# ESP32_with_USBC.net
KiCad netlist of a schematic drawn in Altium Designer
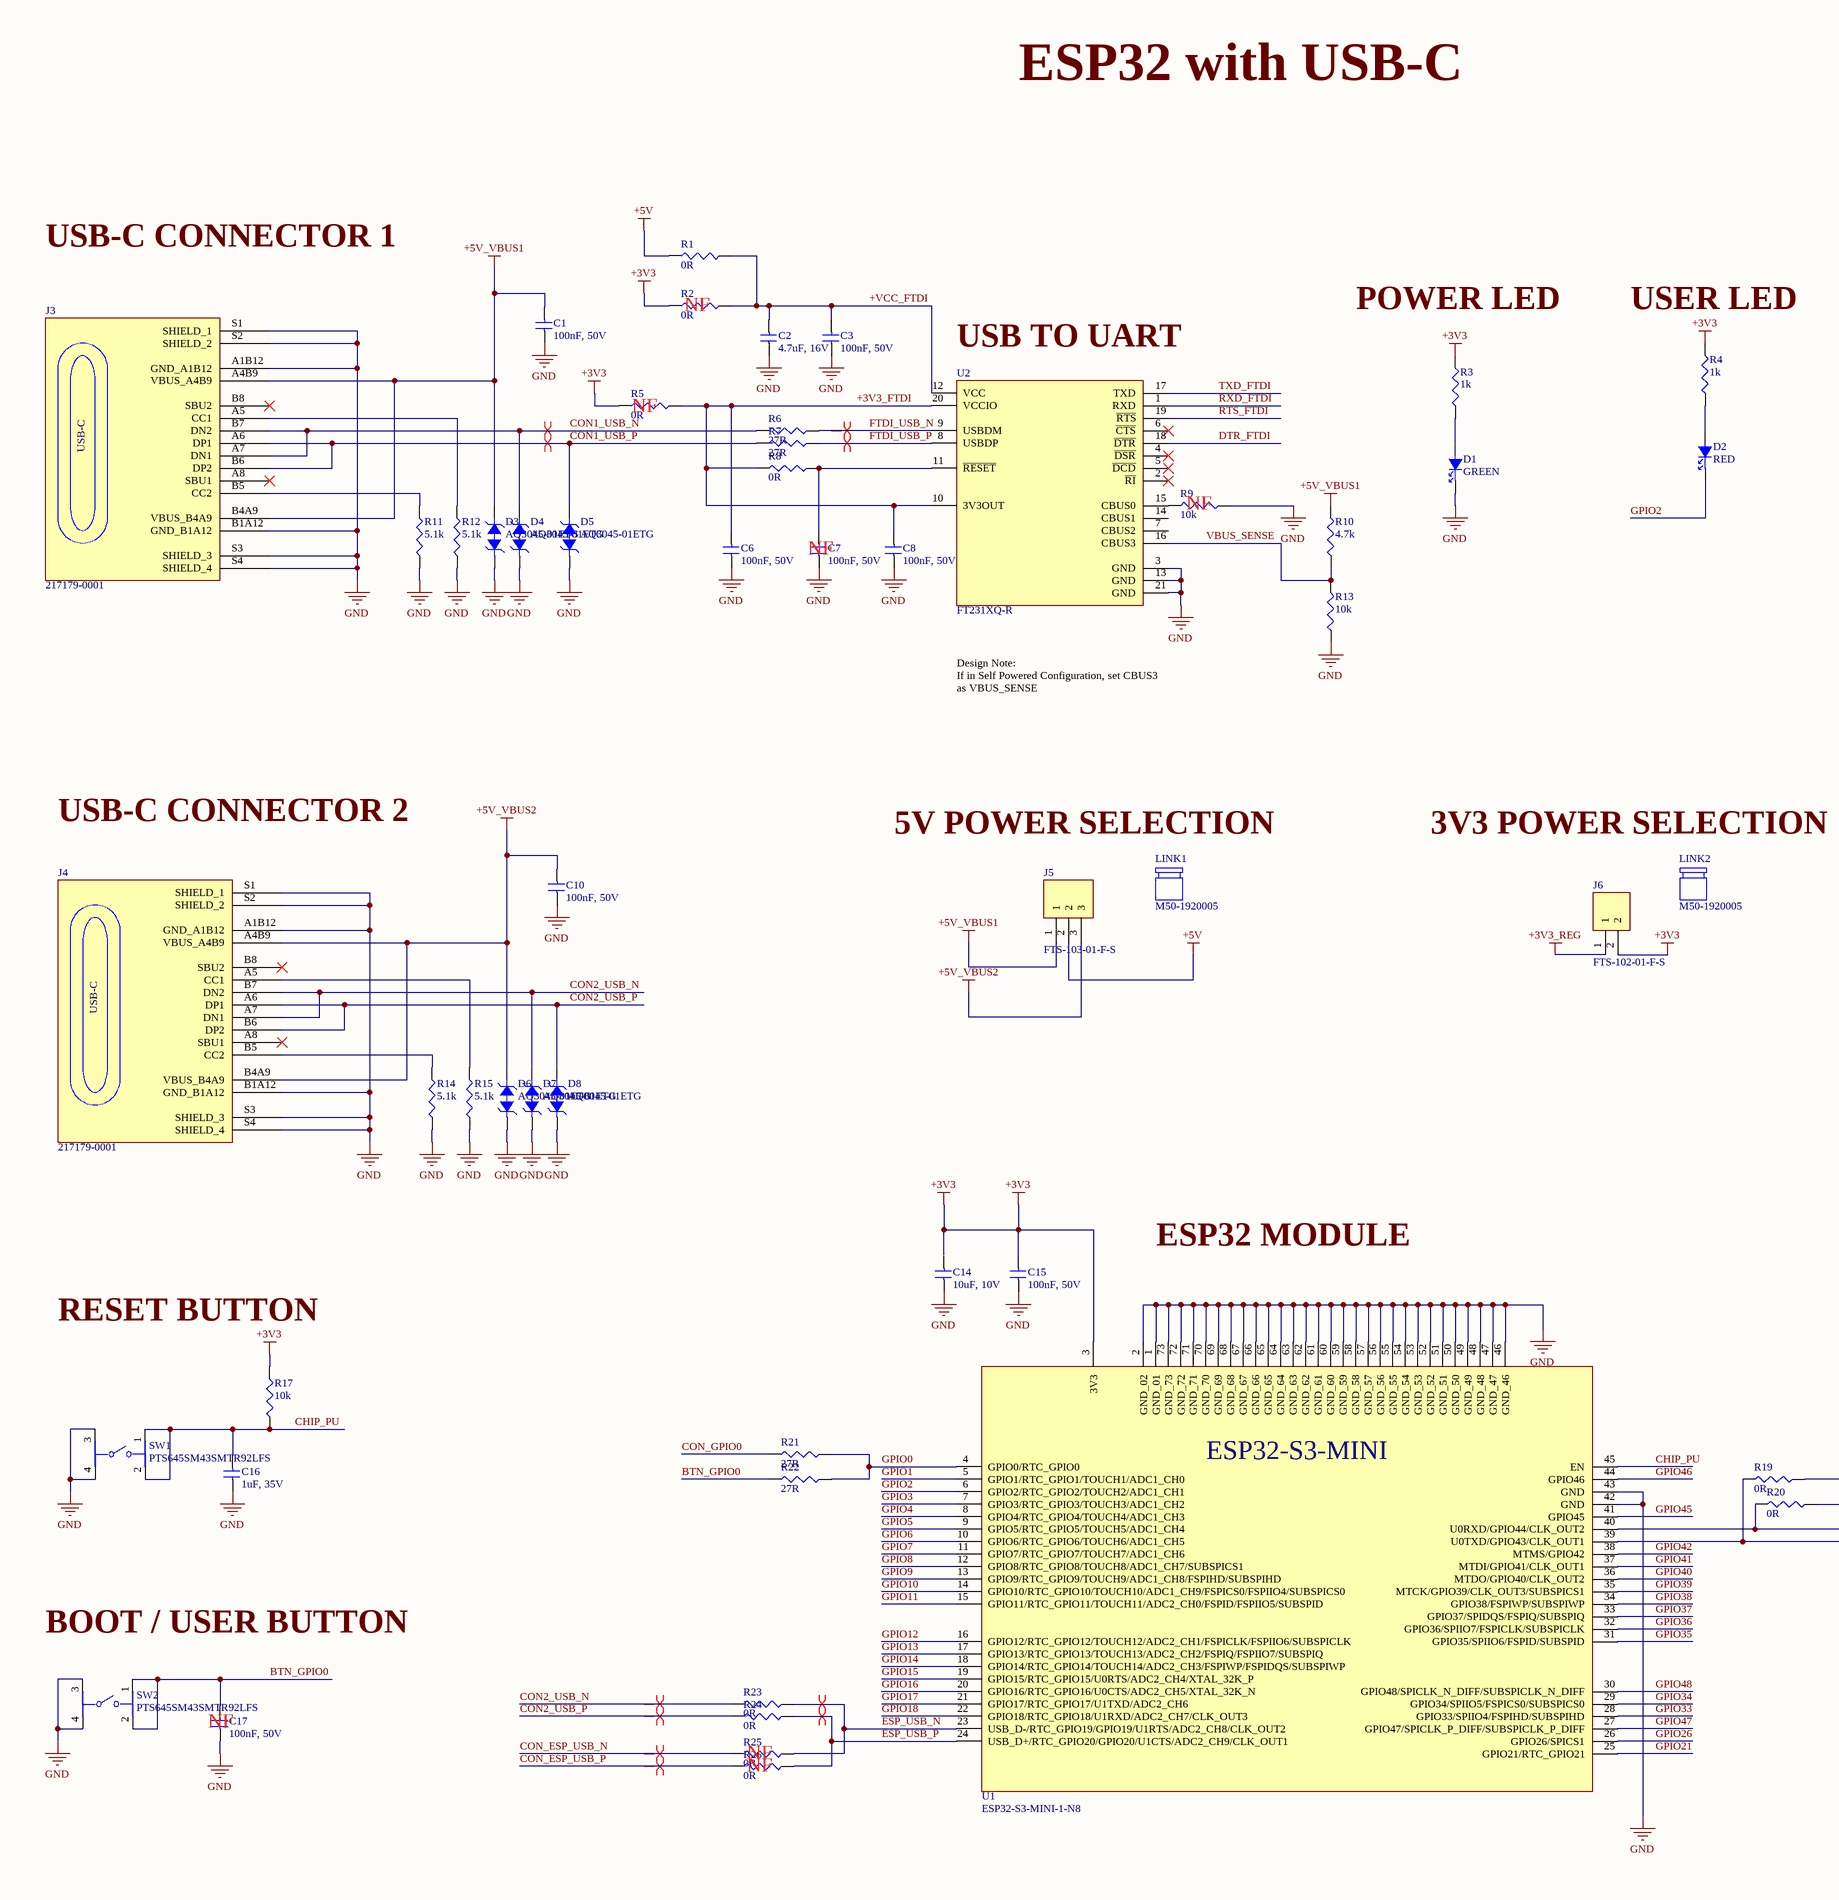
[diagram p0: ESP32 with USBC.SchDoc, left]
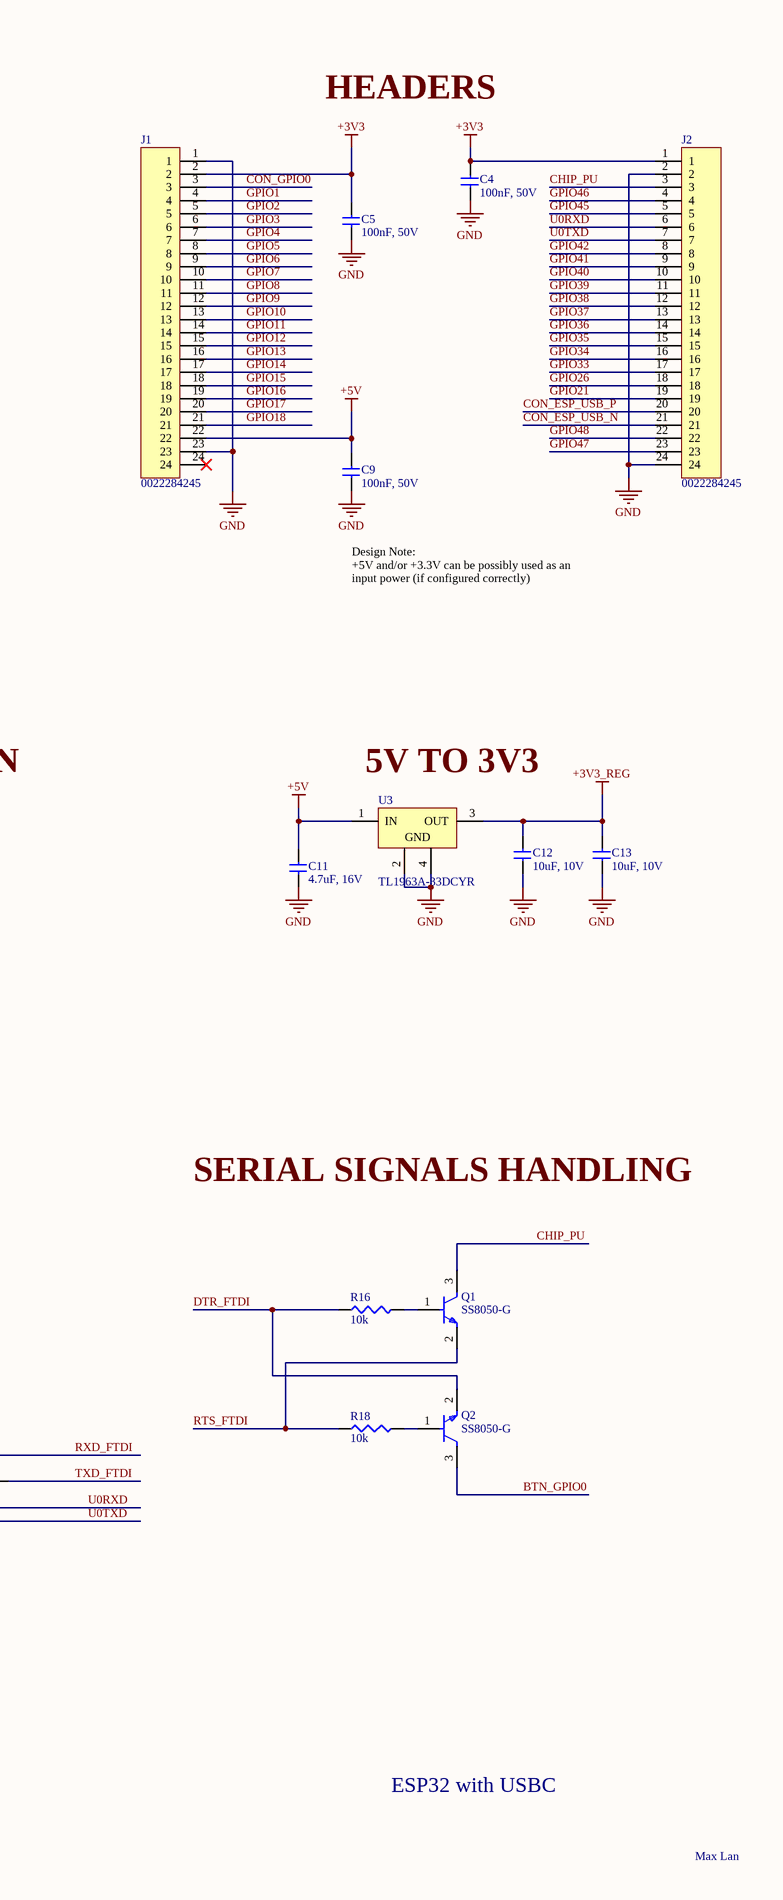
[diagram p1: ESP32 with USBC.SchDoc, right]

(export (version "E")
  (design (tool "Eeschema 10.0.6"))
  (components
    (comp (ref "C1")
      (value "100nF, 50V")
      (footprint "CAPC1005X55N")
      (description "CAP CER 0.1UF 50V X7R 0402")
      (fields
        (field (name "MANUFACTURER") "Samsung Electro-Mechanics")
        (field (name "MANUFACTURER PART NUMBER") "CL05B104KB5NNNC")
      )
      (libsource (lib "Schlib") (part "CL05B104KB5NNNC"))
    )
    (comp (ref "C2")
      (value "4.7uF, 16V")
      (footprint "CAPC1005X55N")
      (description "CAP CER 4.7UF 16V X5R 0402")
      (fields
        (field (name "MANUFACTURER") "Samsung Electro-Mechanics")
        (field (name "MANUFACTURER PART NUMBER") "CL05A475MO5NUNC")
      )
      (libsource (lib "Schlib") (part "CL05A475MO5NUNC"))
    )
    (comp (ref "C3")
      (value "100nF, 50V")
      (footprint "CAPC1005X55N")
      (description "CAP CER 0.1UF 50V X7R 0402")
      (fields
        (field (name "MANUFACTURER") "Samsung Electro-Mechanics")
        (field (name "MANUFACTURER PART NUMBER") "CL05B104KB5NNNC")
      )
      (libsource (lib "Schlib") (part "CL05B104KB5NNNC"))
    )
    (comp (ref "C4")
      (value "100nF, 50V")
      (footprint "CAPC1005X55N")
      (description "CAP CER 0.1UF 50V X7R 0402")
      (fields
        (field (name "MANUFACTURER") "Samsung Electro-Mechanics")
        (field (name "MANUFACTURER PART NUMBER") "CL05B104KB5NNNC")
      )
      (libsource (lib "Schlib") (part "CL05B104KB5NNNC"))
    )
    (comp (ref "C5")
      (value "100nF, 50V")
      (footprint "CAPC1005X55N")
      (description "CAP CER 0.1UF 50V X7R 0402")
      (fields
        (field (name "MANUFACTURER") "Samsung Electro-Mechanics")
        (field (name "MANUFACTURER PART NUMBER") "CL05B104KB5NNNC")
      )
      (libsource (lib "Schlib") (part "CL05B104KB5NNNC"))
    )
    (comp (ref "C6")
      (value "100nF, 50V")
      (footprint "CAPC1005X55N")
      (description "CAP CER 0.1UF 50V X7R 0402")
      (fields
        (field (name "MANUFACTURER") "Samsung Electro-Mechanics")
        (field (name "MANUFACTURER PART NUMBER") "CL05B104KB5NNNC")
      )
      (libsource (lib "Schlib") (part "CL05B104KB5NNNC"))
    )
    (comp (ref "C7")
      (value "100nF, 50V")
      (footprint "CAPC1005X55N")
      (description "CAP CER 0.1UF 50V X7R 0402")
      (fields
        (field (name "MANUFACTURER") "Samsung Electro-Mechanics")
        (field (name "MANUFACTURER PART NUMBER") "CL05B104KB5NNNC")
      )
      (libsource (lib "Schlib") (part "CL05B104KB5NNNC"))
    )
    (comp (ref "C8")
      (value "100nF, 50V")
      (footprint "CAPC1005X55N")
      (description "CAP CER 0.1UF 50V X7R 0402")
      (fields
        (field (name "MANUFACTURER") "Samsung Electro-Mechanics")
        (field (name "MANUFACTURER PART NUMBER") "CL05B104KB5NNNC")
      )
      (libsource (lib "Schlib") (part "CL05B104KB5NNNC"))
    )
    (comp (ref "C9")
      (value "100nF, 50V")
      (footprint "CAPC1005X55N")
      (description "CAP CER 0.1UF 50V X7R 0402")
      (fields
        (field (name "MANUFACTURER") "Samsung Electro-Mechanics")
        (field (name "MANUFACTURER PART NUMBER") "CL05B104KB5NNNC")
      )
      (libsource (lib "Schlib") (part "CL05B104KB5NNNC"))
    )
    (comp (ref "C10")
      (value "100nF, 50V")
      (footprint "CAPC1005X55N")
      (description "CAP CER 0.1UF 50V X7R 0402")
      (fields
        (field (name "MANUFACTURER") "Samsung Electro-Mechanics")
        (field (name "MANUFACTURER PART NUMBER") "CL05B104KB5NNNC")
      )
      (libsource (lib "Schlib") (part "CL05B104KB5NNNC"))
    )
    (comp (ref "C11")
      (value "4.7uF, 16V")
      (footprint "CAPC1005X55N")
      (description "CAP CER 4.7UF 16V X5R 0402")
      (fields
        (field (name "MANUFACTURER") "Samsung Electro-Mechanics")
        (field (name "MANUFACTURER PART NUMBER") "CL05A475MO5NUNC")
      )
      (libsource (lib "Schlib") (part "CL05A475MO5NUNC"))
    )
    (comp (ref "C12")
      (value "10uF, 10V")
      (footprint "CAPC1005X55N")
      (description "10 µF ±20% 10V Ceramic Capacitor X5R 0402 (1005 Metric)")
      (fields
        (field (name "MANUFACTURER") "Samsung Electro-Mechanics")
        (field (name "MANUFACTURER PART NUMBER") "CL05A106MP5NRNC")
      )
      (libsource (lib "Schlib") (part "CL05A106MP5NRNC"))
    )
    (comp (ref "C13")
      (value "10uF, 10V")
      (footprint "CAPC1005X55N")
      (description "10 µF ±20% 10V Ceramic Capacitor X5R 0402 (1005 Metric)")
      (fields
        (field (name "MANUFACTURER") "Samsung Electro-Mechanics")
        (field (name "MANUFACTURER PART NUMBER") "CL05A106MP5NRNC")
      )
      (libsource (lib "Schlib") (part "CL05A106MP5NRNC"))
    )
    (comp (ref "C14")
      (value "10uF, 10V")
      (footprint "CAPC1005X55N")
      (description "10 µF ±20% 10V Ceramic Capacitor X5R 0402 (1005 Metric)")
      (fields
        (field (name "MANUFACTURER") "Samsung Electro-Mechanics")
        (field (name "MANUFACTURER PART NUMBER") "CL05A106MP5NRNC")
      )
      (libsource (lib "Schlib") (part "CL05A106MP5NRNC"))
    )
    (comp (ref "C15")
      (value "100nF, 50V")
      (footprint "CAPC1005X55N")
      (description "CAP CER 0.1UF 50V X7R 0402")
      (fields
        (field (name "MANUFACTURER") "Samsung Electro-Mechanics")
        (field (name "MANUFACTURER PART NUMBER") "CL05B104KB5NNNC")
      )
      (libsource (lib "Schlib") (part "CL05B104KB5NNNC"))
    )
    (comp (ref "C16")
      (value "1uF, 35V")
      (footprint "CAPC1005X55N")
      (description "CAP CER 1UF 35V X5R 0402")
      (fields
        (field (name "MANUFACTURER") "Samsung Electro-Mechanics")
        (field (name "MANUFACTURER PART NUMBER") "CL05A105KL5NRNC")
      )
      (libsource (lib "Schlib") (part "CL05A105KL5NRNC"))
    )
    (comp (ref "C17")
      (value "100nF, 50V")
      (footprint "CAPC1005X55N")
      (description "CAP CER 0.1UF 50V X7R 0402")
      (fields
        (field (name "MANUFACTURER") "Samsung Electro-Mechanics")
        (field (name "MANUFACTURER PART NUMBER") "CL05B104KB5NNNC")
      )
      (libsource (lib "Schlib") (part "CL05B104KB5NNNC"))
    )
    (comp (ref "D1")
      (value "GREEN")
      (footprint "LED0402G")
      (description "LED YLW-GRN 0402 SMD")
      (fields
        (field (name "MANUFACTURER") "Vishay")
        (field (name "MANUFACTURER PART NUMBER") "VLMG1500-GS08")
      )
      (libsource (lib "Schlib") (part "VLMG1500-GS08"))
    )
    (comp (ref "D2")
      (value "RED")
      (footprint "LED0402R")
      (description "LED RED 0402 SMD")
      (fields
        (field (name "MANUFACTURER") "Vishay")
        (field (name "MANUFACTURER PART NUMBER") "VLMS1500-GS08")
      )
      (libsource (lib "Schlib") (part "VLMS1500-GS08"))
    )
    (comp (ref "D3")
      (value "AQ3045-01ETG")
      (footprint "SOD882")
      (description "TVS DIODE 5.3VWM 12VC SOD882")
      (fields (field (name "MANUFACTURER") "Littelfuse") (field (name "LCSC PART NUMBER") "C3710326"))
      (libsource (lib "Schlib") (part "AQ3045-01ETG"))
    )
    (comp (ref "D4")
      (value "AQ3045-01ETG")
      (footprint "SOD882")
      (description "TVS DIODE 5.3VWM 12VC SOD882")
      (fields (field (name "MANUFACTURER") "Littelfuse") (field (name "LCSC PART NUMBER") "C3710326"))
      (libsource (lib "Schlib") (part "AQ3045-01ETG"))
    )
    (comp (ref "D5")
      (value "AQ3045-01ETG")
      (footprint "SOD882")
      (description "TVS DIODE 5.3VWM 12VC SOD882")
      (fields (field (name "MANUFACTURER") "Littelfuse") (field (name "LCSC PART NUMBER") "C3710326"))
      (libsource (lib "Schlib") (part "AQ3045-01ETG"))
    )
    (comp (ref "D6")
      (value "AQ3045-01ETG")
      (footprint "SOD882")
      (description "TVS DIODE 5.3VWM 12VC SOD882")
      (fields (field (name "MANUFACTURER") "Littelfuse") (field (name "LCSC PART NUMBER") "C3710326"))
      (libsource (lib "Schlib") (part "AQ3045-01ETG"))
    )
    (comp (ref "D7")
      (value "AQ3045-01ETG")
      (footprint "SOD882")
      (description "TVS DIODE 5.3VWM 12VC SOD882")
      (fields (field (name "MANUFACTURER") "Littelfuse") (field (name "LCSC PART NUMBER") "C3710326"))
      (libsource (lib "Schlib") (part "AQ3045-01ETG"))
    )
    (comp (ref "D8")
      (value "AQ3045-01ETG")
      (footprint "SOD882")
      (description "TVS DIODE 5.3VWM 12VC SOD882")
      (fields (field (name "MANUFACTURER") "Littelfuse") (field (name "LCSC PART NUMBER") "C3710326"))
      (libsource (lib "Schlib") (part "AQ3045-01ETG"))
    )
    (comp (ref "J1")
      (value "0022284245")
      (footprint "HDR_1X24_2.54MM")
      (description "CONN HEADER VERT 24POS 2.54MM")
      (fields (field (name "MANUFACTURER") "Molex") (field (name "MANUFACTURER PART NUMBER") "22-28-4245"))
      (libsource (lib "Schlib") (part "0022284245"))
    )
    (comp (ref "J2")
      (value "0022284245")
      (footprint "HDR_1X24_2.54MM")
      (description "CONN HEADER VERT 24POS 2.54MM")
      (fields (field (name "MANUFACTURER") "Molex") (field (name "MANUFACTURER PART NUMBER") "22-28-4245"))
      (libsource (lib "") (part "0022284245_1"))
    )
    (comp (ref "J3")
      (value "217179-0001")
      (footprint "FP-2171790001-MFG")
      (description "CONN RCP USB2.0 TYP C 24P SMD RA")
      (fields (field (name "MANUFACTURER") "Molex") (field (name "LCSC PART NUMBER") "C3197684"))
      (libsource (lib "Schlib") (part "217179-0001"))
    )
    (comp (ref "J4")
      (value "217179-0001")
      (footprint "FP-2171790001-MFG")
      (description "CONN RCP USB2.0 TYP C 24P SMD RA")
      (fields (field (name "MANUFACTURER") "Molex") (field (name "LCSC PART NUMBER") "C3197684"))
      (libsource (lib "Schlib") (part "217179-0001"))
    )
    (comp (ref "J5")
      (value "FTS-103-01-F-S")
      (footprint "HDR_1X3_1.27MM")
      (description "CONN HEADER VERT 3POS 1.27MM")
      (fields (field (name "MANUFACTURER") "Samtec") (field (name "LCSC PART NUMBER") "C3333578"))
      (libsource (lib "Schlib") (part "FTS-103-01-F-S"))
    )
    (comp (ref "J6")
      (value "FTS-102-01-F-S")
      (footprint "HDR_1X2_1.27MM")
      (description "CONN HEADER VERT 2POS 1.27MM")
      (fields (field (name "MANUFACTURER") "Samtec") (field (name "LCSC PART NUMBER") "C6045317"))
      (libsource (lib "Schlib") (part "FTS-102-01-F-S"))
    )
    (comp (ref "LINK1")
      (value "M50-1920005")
      (description "CONN SHUNT 1.27MM RED")
      (fields (field (name "MANUFACTURER") "Harwin") (field (name "LCSC PART NUMBER") "C6985646"))
      (libsource (lib "Schlib") (part "M50-1920005"))
    )
    (comp (ref "LINK2")
      (value "M50-1920005")
      (description "CONN SHUNT 1.27MM RED")
      (fields (field (name "MANUFACTURER") "Harwin") (field (name "LCSC PART NUMBER") "C6985646"))
      (libsource (lib "Schlib") (part "M50-1920005"))
    )
    (comp (ref "Q1")
      (value "SS8050-G")
      (footprint "FP-SS8050-G-IPC_B")
      (description "TRANS NPN 25V 1.5A SOT-23-3")
      (fields (field (name "MANUFACTURER") "Comchip") (field (name "LCSC PART NUMBER") "C164886"))
      (libsource (lib "Schlib") (part "SS8050-G"))
    )
    (comp (ref "Q2")
      (value "SS8050-G")
      (footprint "FP-SS8050-G-IPC_B")
      (description "TRANS NPN 25V 1.5A SOT-23-3")
      (fields (field (name "MANUFACTURER") "Comchip") (field (name "LCSC PART NUMBER") "C164886"))
      (libsource (lib "Schlib") (part "SS8050-G"))
    )
    (comp (ref "R1")
      (value "0R")
      (footprint "RESC1005X37N")
      (description "RES 0 OHM JUMPER 1/16W 0402")
      (fields
        (field (name "MANUFACTURER") "Yageo Group")
        (field (name "MANUFACTURER PART NUMBER") "RC0402JR-070RL")
      )
      (libsource (lib "Schlib") (part "RC0402JR-070RL"))
    )
    (comp (ref "R2")
      (value "0R")
      (footprint "RESC1005X37N")
      (description "RES 0 OHM JUMPER 1/16W 0402")
      (fields
        (field (name "MANUFACTURER") "Yageo Group")
        (field (name "MANUFACTURER PART NUMBER") "RC0402JR-070RL")
      )
      (libsource (lib "Schlib") (part "RC0402JR-070RL"))
    )
    (comp (ref "R3")
      (value "1k")
      (footprint "RESC1005X37N")
      (description "RES 1K OHM 1% 1/16W 0402")
      (fields
        (field (name "MANUFACTURER") "Yageo Group")
        (field (name "MANUFACTURER PART NUMBER") "RC0402FR-071KL")
      )
      (libsource (lib "Schlib") (part "RC0402FR-071KL"))
    )
    (comp (ref "R4")
      (value "1k")
      (footprint "RESC1005X37N")
      (description "RES 1K OHM 1% 1/16W 0402")
      (fields
        (field (name "MANUFACTURER") "Yageo Group")
        (field (name "MANUFACTURER PART NUMBER") "RC0402FR-071KL")
      )
      (libsource (lib "Schlib") (part "RC0402FR-071KL"))
    )
    (comp (ref "R5")
      (value "0R")
      (footprint "RESC1005X37N")
      (description "RES 0 OHM JUMPER 1/16W 0402")
      (fields
        (field (name "MANUFACTURER") "Yageo Group")
        (field (name "MANUFACTURER PART NUMBER") "RC0402JR-070RL")
      )
      (libsource (lib "Schlib") (part "RC0402JR-070RL"))
    )
    (comp (ref "R6")
      (value "27R")
      (footprint "RESC1005X37N")
      (description "RES 27 OHM 1% 1/16W 0402")
      (fields
        (field (name "MANUFACTURER") "Yageo Group")
        (field (name "MANUFACTURER PART NUMBER") "RC0402FR-0727RL")
      )
      (libsource (lib "Schlib") (part "RC0402FR-0727RL"))
    )
    (comp (ref "R7")
      (value "27R")
      (footprint "RESC1005X37N")
      (description "RES 27 OHM 1% 1/16W 0402")
      (fields
        (field (name "MANUFACTURER") "Yageo Group")
        (field (name "MANUFACTURER PART NUMBER") "RC0402FR-0727RL")
      )
      (libsource (lib "Schlib") (part "RC0402FR-0727RL"))
    )
    (comp (ref "R8")
      (value "0R")
      (footprint "RESC1005X37N")
      (description "RES 0 OHM JUMPER 1/16W 0402")
      (fields
        (field (name "MANUFACTURER") "Yageo Group")
        (field (name "MANUFACTURER PART NUMBER") "RC0402JR-070RL")
      )
      (libsource (lib "Schlib") (part "RC0402JR-070RL"))
    )
    (comp (ref "R9")
      (value "10k")
      (footprint "RESC1005X37N")
      (description "RES SMD 10K OHM 1% 1/16W 0402")
      (fields
        (field (name "MANUFACTURER") "Yageo Group")
        (field (name "MANUFACTURER PART NUMBER") "AF0402FR-0710KL")
      )
      (libsource (lib "Schlib") (part "AF0402FR-0710KL"))
    )
    (comp (ref "R10")
      (value "4.7k")
      (footprint "RESC1005X37N")
      (description "RES SMD 4.7K OHM 1% 1/16W 0402")
      (fields
        (field (name "MANUFACTURER") "Yageo Group")
        (field (name "MANUFACTURER PART NUMBER") "RT0402FRE074K7L")
      )
      (libsource (lib "Schlib") (part "RT0402FRE074K7L"))
    )
    (comp (ref "R11")
      (value "5.1k")
      (footprint "RESC1005X37N")
      (description "RES SMD 5.1K OHM 1% 1/16W 0402")
      (fields
        (field (name "MANUFACTURER") "Yageo Group")
        (field (name "MANUFACTURER PART NUMBER") "AC0402FR-075K1L")
      )
      (libsource (lib "Schlib") (part "AC0402FR-075K1L"))
    )
    (comp (ref "R12")
      (value "5.1k")
      (footprint "RESC1005X37N")
      (description "RES SMD 5.1K OHM 1% 1/16W 0402")
      (fields
        (field (name "MANUFACTURER") "Yageo Group")
        (field (name "MANUFACTURER PART NUMBER") "AC0402FR-075K1L")
      )
      (libsource (lib "Schlib") (part "AC0402FR-075K1L"))
    )
    (comp (ref "R13")
      (value "10k")
      (footprint "RESC1005X37N")
      (description "RES SMD 10K OHM 1% 1/16W 0402")
      (fields
        (field (name "MANUFACTURER") "Yageo Group")
        (field (name "MANUFACTURER PART NUMBER") "AF0402FR-0710KL")
      )
      (libsource (lib "Schlib") (part "AF0402FR-0710KL"))
    )
    (comp (ref "R14")
      (value "5.1k")
      (footprint "RESC1005X37N")
      (description "RES SMD 5.1K OHM 1% 1/16W 0402")
      (fields
        (field (name "MANUFACTURER") "Yageo Group")
        (field (name "MANUFACTURER PART NUMBER") "AC0402FR-075K1L")
      )
      (libsource (lib "Schlib") (part "AC0402FR-075K1L"))
    )
    (comp (ref "R15")
      (value "5.1k")
      (footprint "RESC1005X37N")
      (description "RES SMD 5.1K OHM 1% 1/16W 0402")
      (fields
        (field (name "MANUFACTURER") "Yageo Group")
        (field (name "MANUFACTURER PART NUMBER") "AC0402FR-075K1L")
      )
      (libsource (lib "Schlib") (part "AC0402FR-075K1L"))
    )
    (comp (ref "R16")
      (value "10k")
      (footprint "RESC1005X37N")
      (description "RES SMD 10K OHM 1% 1/16W 0402")
      (fields
        (field (name "MANUFACTURER") "Yageo Group")
        (field (name "MANUFACTURER PART NUMBER") "AF0402FR-0710KL")
      )
      (libsource (lib "Schlib") (part "AF0402FR-0710KL"))
    )
    (comp (ref "R17")
      (value "10k")
      (footprint "RESC1005X37N")
      (description "RES SMD 10K OHM 1% 1/16W 0402")
      (fields
        (field (name "MANUFACTURER") "Yageo Group")
        (field (name "MANUFACTURER PART NUMBER") "AF0402FR-0710KL")
      )
      (libsource (lib "Schlib") (part "AF0402FR-0710KL"))
    )
    (comp (ref "R18")
      (value "10k")
      (footprint "RESC1005X37N")
      (description "RES SMD 10K OHM 1% 1/16W 0402")
      (fields
        (field (name "MANUFACTURER") "Yageo Group")
        (field (name "MANUFACTURER PART NUMBER") "AF0402FR-0710KL")
      )
      (libsource (lib "Schlib") (part "AF0402FR-0710KL"))
    )
    (comp (ref "R19")
      (value "0R")
      (footprint "RESC1005X37N")
      (description "RES 0 OHM JUMPER 1/16W 0402")
      (fields
        (field (name "MANUFACTURER") "Yageo Group")
        (field (name "MANUFACTURER PART NUMBER") "RC0402JR-070RL")
      )
      (libsource (lib "Schlib") (part "RC0402JR-070RL"))
    )
    (comp (ref "R20")
      (value "0R")
      (footprint "RESC1005X37N")
      (description "RES 0 OHM JUMPER 1/16W 0402")
      (fields
        (field (name "MANUFACTURER") "Yageo Group")
        (field (name "MANUFACTURER PART NUMBER") "RC0402JR-070RL")
      )
      (libsource (lib "Schlib") (part "RC0402JR-070RL"))
    )
    (comp (ref "R21")
      (value "27R")
      (footprint "RESC1005X37N")
      (description "RES 27 OHM 1% 1/16W 0402")
      (fields
        (field (name "MANUFACTURER") "Yageo Group")
        (field (name "MANUFACTURER PART NUMBER") "RC0402FR-0727RL")
      )
      (libsource (lib "Schlib") (part "RC0402FR-0727RL"))
    )
    (comp (ref "R22")
      (value "27R")
      (footprint "RESC1005X37N")
      (description "RES 27 OHM 1% 1/16W 0402")
      (fields
        (field (name "MANUFACTURER") "Yageo Group")
        (field (name "MANUFACTURER PART NUMBER") "RC0402FR-0727RL")
      )
      (libsource (lib "Schlib") (part "RC0402FR-0727RL"))
    )
    (comp (ref "R23")
      (value "0R")
      (footprint "RESC1005X37N")
      (description "RES 0 OHM JUMPER 1/16W 0402")
      (fields
        (field (name "MANUFACTURER") "Yageo Group")
        (field (name "MANUFACTURER PART NUMBER") "RC0402JR-070RL")
      )
      (libsource (lib "Schlib") (part "RC0402JR-070RL"))
    )
    (comp (ref "R24")
      (value "0R")
      (footprint "RESC1005X37N")
      (description "RES 0 OHM JUMPER 1/16W 0402")
      (fields
        (field (name "MANUFACTURER") "Yageo Group")
        (field (name "MANUFACTURER PART NUMBER") "RC0402JR-070RL")
      )
      (libsource (lib "Schlib") (part "RC0402JR-070RL"))
    )
    (comp (ref "R25")
      (value "0R")
      (footprint "RESC1005X37N")
      (description "RES 0 OHM JUMPER 1/16W 0402")
      (fields
        (field (name "MANUFACTURER") "Yageo Group")
        (field (name "MANUFACTURER PART NUMBER") "RC0402JR-070RL")
      )
      (libsource (lib "Schlib") (part "RC0402JR-070RL"))
    )
    (comp (ref "R26")
      (value "0R")
      (footprint "RESC1005X37N")
      (description "RES 0 OHM JUMPER 1/16W 0402")
      (fields
        (field (name "MANUFACTURER") "Yageo Group")
        (field (name "MANUFACTURER PART NUMBER") "RC0402JR-070RL")
      )
      (libsource (lib "Schlib") (part "RC0402JR-070RL"))
    )
    (comp (ref "SW1")
      (value "PTS645SM43SMTR92LFS")
      (footprint "FP-PTS645SM43SMTR92LFS-MFG")
      (description "SWITCH TACTILE SPST-NO 0.05A 12V")
      (fields (field (name "MANUFACTURER") "C&K Components") (field (name "LCSC PART NUMBER") "C221880"))
      (libsource (lib "Schlib") (part "PTS645SM43SMTR92LFS"))
    )
    (comp (ref "SW2")
      (value "PTS645SM43SMTR92LFS")
      (footprint "FP-PTS645SM43SMTR92LFS-MFG")
      (description "SWITCH TACTILE SPST-NO 0.05A 12V")
      (fields (field (name "MANUFACTURER") "C&K Components") (field (name "LCSC PART NUMBER") "C221880"))
      (libsource (lib "Schlib") (part "PTS645SM43SMTR92LFS"))
    )
    (comp (ref "U1")
      (value "ESP32-S3-MINI-1-N8")
      (footprint "XCVR_ESP32-S3-MINI-1-N8")
      (description "SMD module, ESP32-S3FN8, 8 MB SPI flash, PCB antenna")
      (fields (field (name "MANUFACTURER") "Espressif Systems") (field (name "LCSC PART NUMBER") "C2913206"))
      (libsource (lib "Schlib") (part "ESP32-S3-MINI-1-N8"))
    )
    (comp (ref "U2")
      (value "FT231XQ-R")
      (footprint "FP-QFN-20-IPC_B")
      (description "IC USB SERIAL FULL UART 20QFN")
      (fields (field (name "MANUFACTURER") "FTDI") (field (name "LCSC PART NUMBER") "C132159"))
      (libsource (lib "Schlib") (part "FT231XQ-R"))
    )
    (comp (ref "U3")
      (value "TL1963A-33DCYR")
      (footprint "DCY0004A_N")
      (description "IC REG LIN 3.3V 1.5A SOT-223-4")
      (fields (field (name "MANUFACTURER") "Texas Instruments") (field (name "LCSC PART NUMBER") "C181262"))
      (libsource (lib "Schlib") (part "TL1963A-33DCYR"))
    )
  )
  (nets
    (net (code "1") (name "+3V3") (class "Default")
      (node (ref "C15") (pin "2") (pinfunction "2_2") (pintype "passive"))
      (node (ref "C4") (pin "2") (pinfunction "2_2") (pintype "passive"))
      (node (ref "C5") (pin "2") (pinfunction "2_2") (pintype "passive"))
      (node (ref "J1") (pin "2") (pinfunction "2_2") (pintype "passive"))
      (node (ref "J2") (pin "1") (pinfunction "1_1") (pintype "passive"))
      (node (ref "J6") (pin "2") (pinfunction "2_2") (pintype "passive"))
      (node (ref "R17") (pin "2") (pinfunction "2_2") (pintype "passive"))
      (node (ref "R2") (pin "1") (pinfunction "1_1") (pintype "passive"))
      (node (ref "R3") (pin "2") (pinfunction "2_2") (pintype "passive"))
      (node (ref "R4") (pin "2") (pinfunction "2_2") (pintype "passive"))
      (node (ref "R5") (pin "1") (pinfunction "1_1") (pintype "passive"))
      (node (ref "U1") (pin "3") (pinfunction "3V3_3") (pintype "passive"))
    )
    (net (code "2") (name "+3V3_REG") (class "Default")
      (node (ref "C12") (pin "2") (pinfunction "2_2") (pintype "passive"))
      (node (ref "C13") (pin "2") (pinfunction "2_2") (pintype "passive"))
      (node (ref "J6") (pin "1") (pinfunction "1_1") (pintype "passive"))
      (node (ref "U3") (pin "3") (pinfunction "OUT_3") (pintype "power_in"))
    )
    (net (code "3") (name "+5V") (class "Default")
      (node (ref "C11") (pin "2") (pinfunction "2_2") (pintype "passive"))
      (node (ref "C9") (pin "2") (pinfunction "2_2") (pintype "passive"))
      (node (ref "J1") (pin "22") (pinfunction "22_22") (pintype "passive"))
      (node (ref "J5") (pin "2") (pinfunction "2_2") (pintype "passive"))
      (node (ref "R1") (pin "1") (pinfunction "1_1") (pintype "passive"))
      (node (ref "U3") (pin "1") (pinfunction "IN_1") (pintype "power_in"))
    )
    (net (code "4") (name "+5V_VBUS1") (class "Default")
      (node (ref "C1") (pin "2") (pinfunction "2_2") (pintype "passive"))
      (node (ref "D3") (pin "2") (pinfunction "2_2") (pintype "passive"))
      (node (ref "J3") (pin "A4B9") (pinfunction "VBUS_A4B9_A4B9") (pintype "passive"))
      (node (ref "J3") (pin "B4A9") (pinfunction "VBUS_B4A9_B4A9") (pintype "passive"))
      (node (ref "J5") (pin "1") (pinfunction "1_1") (pintype "passive"))
      (node (ref "R10") (pin "2") (pinfunction "2_2") (pintype "passive"))
    )
    (net (code "5") (name "+5V_VBUS2") (class "Default")
      (node (ref "C10") (pin "2") (pinfunction "2_2") (pintype "passive"))
      (node (ref "D6") (pin "2") (pinfunction "2_2") (pintype "passive"))
      (node (ref "J4") (pin "A4B9") (pinfunction "VBUS_A4B9_A4B9") (pintype "passive"))
      (node (ref "J4") (pin "B4A9") (pinfunction "VBUS_B4A9_B4A9") (pintype "passive"))
      (node (ref "J5") (pin "3") (pinfunction "3_3") (pintype "passive"))
    )
    (net (code "6") (name "/+3V3_FTDI") (class "Default")
      (node (ref "C6") (pin "2") (pinfunction "2_2") (pintype "passive"))
      (node (ref "C8") (pin "2") (pinfunction "2_2") (pintype "passive"))
      (node (ref "R5") (pin "2") (pinfunction "2_2") (pintype "passive"))
      (node (ref "R8") (pin "1") (pinfunction "1_1") (pintype "passive"))
      (node (ref "U2") (pin "10") (pinfunction "3V3OUT_10") (pintype "passive"))
      (node (ref "U2") (pin "20") (pinfunction "VCCIO_20") (pintype "passive"))
    )
    (net (code "7") (name "/+VCC_FTDI") (class "Default")
      (node (ref "C2") (pin "2") (pinfunction "2_2") (pintype "passive"))
      (node (ref "C3") (pin "2") (pinfunction "2_2") (pintype "passive"))
      (node (ref "R1") (pin "2") (pinfunction "2_2") (pintype "passive"))
      (node (ref "R2") (pin "2") (pinfunction "2_2") (pintype "passive"))
      (node (ref "U2") (pin "12") (pinfunction "VCC_12") (pintype "passive"))
    )
    (net (code "8") (name "/BTN_GPIO0") (class "Default")
      (node (ref "C17") (pin "2") (pinfunction "2_2") (pintype "passive"))
      (node (ref "Q2") (pin "3") (pinfunction "C_3") (pintype "passive"))
      (node (ref "R22") (pin "1") (pinfunction "1_1") (pintype "passive"))
      (node (ref "SW2") (pin "1") (pinfunction "1_1") (pintype "passive"))
      (node (ref "SW2") (pin "2") (pinfunction "2_2") (pintype "passive"))
    )
    (net (code "9") (name "/CHIP_PU") (class "Default")
      (node (ref "C16") (pin "2") (pinfunction "2_2") (pintype "passive"))
      (node (ref "J2") (pin "3") (pinfunction "3_3") (pintype "passive"))
      (node (ref "Q1") (pin "3") (pinfunction "C_3") (pintype "passive"))
      (node (ref "R17") (pin "1") (pinfunction "1_1") (pintype "passive"))
      (node (ref "SW1") (pin "1") (pinfunction "1_1") (pintype "passive"))
      (node (ref "SW1") (pin "2") (pinfunction "2_2") (pintype "passive"))
      (node (ref "U1") (pin "45") (pinfunction "EN_45") (pintype "passive"))
    )
    (net (code "10") (name "/CON1_USB_N") (class "Default")
      (node (ref "D4") (pin "2") (pinfunction "2_2") (pintype "passive"))
      (node (ref "J3") (pin "A7") (pinfunction "DN1_A7") (pintype "passive"))
      (node (ref "J3") (pin "B7") (pinfunction "DN2_B7") (pintype "passive"))
      (node (ref "R6") (pin "1") (pinfunction "1_1") (pintype "passive"))
    )
    (net (code "11") (name "/CON1_USB_P") (class "Default")
      (node (ref "D5") (pin "2") (pinfunction "2_2") (pintype "passive"))
      (node (ref "J3") (pin "A6") (pinfunction "DP1_A6") (pintype "passive"))
      (node (ref "J3") (pin "B6") (pinfunction "DP2_B6") (pintype "passive"))
      (node (ref "R7") (pin "1") (pinfunction "1_1") (pintype "passive"))
    )
    (net (code "12") (name "/CON2_USB_N") (class "Default")
      (node (ref "D7") (pin "2") (pinfunction "2_2") (pintype "passive"))
      (node (ref "J4") (pin "A7") (pinfunction "DN1_A7") (pintype "passive"))
      (node (ref "J4") (pin "B7") (pinfunction "DN2_B7") (pintype "passive"))
      (node (ref "R23") (pin "1") (pinfunction "1_1") (pintype "passive"))
    )
    (net (code "13") (name "/CON2_USB_P") (class "Default")
      (node (ref "D8") (pin "2") (pinfunction "2_2") (pintype "passive"))
      (node (ref "J4") (pin "A6") (pinfunction "DP1_A6") (pintype "passive"))
      (node (ref "J4") (pin "B6") (pinfunction "DP2_B6") (pintype "passive"))
      (node (ref "R24") (pin "1") (pinfunction "1_1") (pintype "passive"))
    )
    (net (code "14") (name "/CON_ESP_USB_N") (class "Default")
      (node (ref "J2") (pin "21") (pinfunction "21_21") (pintype "passive"))
      (node (ref "R25") (pin "1") (pinfunction "1_1") (pintype "passive"))
    )
    (net (code "15") (name "/CON_ESP_USB_P") (class "Default")
      (node (ref "J2") (pin "20") (pinfunction "20_20") (pintype "passive"))
      (node (ref "R26") (pin "1") (pinfunction "1_1") (pintype "passive"))
    )
    (net (code "16") (name "/CON_GPIO0") (class "Default")
      (node (ref "J1") (pin "3") (pinfunction "3_3") (pintype "passive"))
      (node (ref "R21") (pin "1") (pinfunction "1_1") (pintype "passive"))
    )
    (net (code "17") (name "/DTR_FTDI") (class "Default")
      (node (ref "Q2") (pin "2") (pinfunction "E_2") (pintype "passive"))
      (node (ref "R16") (pin "2") (pinfunction "2_2") (pintype "passive"))
      (node (ref "U2") (pin "18") (pinfunction "~{DTR}_18") (pintype "passive"))
    )
    (net (code "18") (name "/ESP_USB_N") (class "Default")
      (node (ref "R23") (pin "2") (pinfunction "2_2") (pintype "passive"))
      (node (ref "R25") (pin "2") (pinfunction "2_2") (pintype "passive"))
      (node (ref "U1") (pin "23") (pinfunction "USB_D-/RTC_GPIO19/GPIO19/U1RTS/ADC2_CH8/CLK_OUT2_23") (pintype "passive"))
    )
    (net (code "19") (name "/ESP_USB_P") (class "Default")
      (node (ref "R24") (pin "2") (pinfunction "2_2") (pintype "passive"))
      (node (ref "R26") (pin "2") (pinfunction "2_2") (pintype "passive"))
      (node (ref "U1") (pin "24") (pinfunction "USB_D+/RTC_GPIO20/GPIO20/U1CTS/ADC2_CH9/CLK_OUT1_24") (pintype "passive"))
    )
    (net (code "20") (name "/FTDI_USB_N") (class "Default")
      (node (ref "R6") (pin "2") (pinfunction "2_2") (pintype "passive"))
      (node (ref "U2") (pin "9") (pinfunction "USBDM_9") (pintype "passive"))
    )
    (net (code "21") (name "/FTDI_USB_P") (class "Default")
      (node (ref "R7") (pin "2") (pinfunction "2_2") (pintype "passive"))
      (node (ref "U2") (pin "8") (pinfunction "USBDP_8") (pintype "passive"))
    )
    (net (code "22") (name "/GPIO0") (class "Default")
      (node (ref "R21") (pin "2") (pinfunction "2_2") (pintype "passive"))
      (node (ref "R22") (pin "2") (pinfunction "2_2") (pintype "passive"))
      (node (ref "U1") (pin "4") (pinfunction "GPIO0/RTC_GPIO0_4") (pintype "passive"))
    )
    (net (code "23") (name "/GPIO1") (class "Default")
      (node (ref "J1") (pin "4") (pinfunction "4_4") (pintype "passive"))
      (node (ref "U1") (pin "5") (pinfunction "GPIO1/RTC_GPIO1/TOUCH1/ADC1_CH0_5") (pintype "passive"))
    )
    (net (code "24") (name "/GPIO2") (class "Default")
      (node (ref "D2") (pin "1") (pinfunction "1_1") (pintype "passive"))
      (node (ref "J1") (pin "5") (pinfunction "5_5") (pintype "passive"))
      (node (ref "U1") (pin "6") (pinfunction "GPIO2/RTC_GPIO2/TOUCH2/ADC1_CH1_6") (pintype "passive"))
    )
    (net (code "25") (name "/GPIO3") (class "Default")
      (node (ref "J1") (pin "6") (pinfunction "6_6") (pintype "passive"))
      (node (ref "U1") (pin "7") (pinfunction "GPIO3/RTC_GPIO3/TOUCH3/ADC1_CH2_7") (pintype "passive"))
    )
    (net (code "26") (name "/GPIO4") (class "Default")
      (node (ref "J1") (pin "7") (pinfunction "7_7") (pintype "passive"))
      (node (ref "U1") (pin "8") (pinfunction "GPIO4/RTC_GPIO4/TOUCH4/ADC1_CH3_8") (pintype "passive"))
    )
    (net (code "27") (name "/GPIO5") (class "Default")
      (node (ref "J1") (pin "8") (pinfunction "8_8") (pintype "passive"))
      (node (ref "U1") (pin "9") (pinfunction "GPIO5/RTC_GPIO5/TOUCH5/ADC1_CH4_9") (pintype "passive"))
    )
    (net (code "28") (name "/GPIO6") (class "Default")
      (node (ref "J1") (pin "9") (pinfunction "9_9") (pintype "passive"))
      (node (ref "U1") (pin "10") (pinfunction "GPIO6/RTC_GPIO6/TOUCH6/ADC1_CH5_10") (pintype "passive"))
    )
    (net (code "29") (name "/GPIO7") (class "Default")
      (node (ref "J1") (pin "10") (pinfunction "10_10") (pintype "passive"))
      (node (ref "U1") (pin "11") (pinfunction "GPIO7/RTC_GPIO7/TOUCH7/ADC1_CH6_11") (pintype "passive"))
    )
    (net (code "30") (name "/GPIO8") (class "Default")
      (node (ref "J1") (pin "11") (pinfunction "11_11") (pintype "passive"))
      (node (ref "U1") (pin "12") (pinfunction "GPIO8/RTC_GPIO8/TOUCH8/ADC1_CH7/SUBSPICS1_12") (pintype "passive"))
    )
    (net (code "31") (name "/GPIO9") (class "Default")
      (node (ref "J1") (pin "12") (pinfunction "12_12") (pintype "passive"))
      (node (ref "U1") (pin "13") (pinfunction "GPIO9/RTC_GPIO9/TOUCH9/ADC1_CH8/FSPIHD/SUBSPIHD_13") (pintype "passive"))
    )
    (net (code "32") (name "/GPIO10") (class "Default")
      (node (ref "J1") (pin "13") (pinfunction "13_13") (pintype "passive"))
      (node (ref "U1") (pin "14") (pinfunction "GPIO10/RTC_GPIO10/TOUCH10/ADC1_CH9/FSPICS0/FSPIIO4/SUBSPICS0_14") (pintype "passive"))
    )
    (net (code "33") (name "/GPIO11") (class "Default")
      (node (ref "J1") (pin "14") (pinfunction "14_14") (pintype "passive"))
      (node (ref "U1") (pin "15") (pinfunction "GPIO11/RTC_GPIO11/TOUCH11/ADC2_CH0/FSPID/FSPIIO5/SUBSPID_15") (pintype "passive"))
    )
    (net (code "34") (name "/GPIO12") (class "Default")
      (node (ref "J1") (pin "15") (pinfunction "15_15") (pintype "passive"))
      (node (ref "U1") (pin "16") (pinfunction "GPIO12/RTC_GPIO12/TOUCH12/ADC2_CH1/FSPICLK/FSPIIO6/SUBSPICLK_16") (pintype "passive"))
    )
    (net (code "35") (name "/GPIO13") (class "Default")
      (node (ref "J1") (pin "16") (pinfunction "16_16") (pintype "passive"))
      (node (ref "U1") (pin "17") (pinfunction "GPIO13/RTC_GPIO13/TOUCH13/ADC2_CH2/FSPIQ/FSPIIO7/SUBSPIQ_17") (pintype "passive"))
    )
    (net (code "36") (name "/GPIO14") (class "Default")
      (node (ref "J1") (pin "17") (pinfunction "17_17") (pintype "passive"))
      (node (ref "U1") (pin "18") (pinfunction "GPIO14/RTC_GPIO14/TOUCH14/ADC2_CH3/FSPIWP/FSPIDQS/SUBSPIWP_18") (pintype "passive"))
    )
    (net (code "37") (name "/GPIO15") (class "Default")
      (node (ref "J1") (pin "18") (pinfunction "18_18") (pintype "passive"))
      (node (ref "U1") (pin "19") (pinfunction "GPIO15/RTC_GPIO15/U0RTS/ADC2_CH4/XTAL_32K_P_19") (pintype "passive"))
    )
    (net (code "38") (name "/GPIO16") (class "Default")
      (node (ref "J1") (pin "19") (pinfunction "19_19") (pintype "passive"))
      (node (ref "U1") (pin "20") (pinfunction "GPIO16/RTC_GPIO16/U0CTS/ADC2_CH5/XTAL_32K_N_20") (pintype "passive"))
    )
    (net (code "39") (name "/GPIO17") (class "Default")
      (node (ref "J1") (pin "20") (pinfunction "20_20") (pintype "passive"))
      (node (ref "U1") (pin "21") (pinfunction "GPIO17/RTC_GPIO17/U1TXD/ADC2_CH6_21") (pintype "passive"))
    )
    (net (code "40") (name "/GPIO18") (class "Default")
      (node (ref "J1") (pin "21") (pinfunction "21_21") (pintype "passive"))
      (node (ref "U1") (pin "22") (pinfunction "GPIO18/RTC_GPIO18/U1RXD/ADC2_CH7/CLK_OUT3_22") (pintype "passive"))
    )
    (net (code "41") (name "/GPIO21") (class "Default")
      (node (ref "J2") (pin "19") (pinfunction "19_19") (pintype "passive"))
      (node (ref "U1") (pin "25") (pinfunction "GPIO21/RTC_GPIO21_25") (pintype "passive"))
    )
    (net (code "42") (name "/GPIO26") (class "Default")
      (node (ref "J2") (pin "18") (pinfunction "18_18") (pintype "passive"))
      (node (ref "U1") (pin "26") (pinfunction "GPIO26/SPICS1_26") (pintype "passive"))
    )
    (net (code "43") (name "/GPIO33") (class "Default")
      (node (ref "J2") (pin "17") (pinfunction "17_17") (pintype "passive"))
      (node (ref "U1") (pin "28") (pinfunction "GPIO33/SPIIO4/FSPIHD/SUBSPIHD_28") (pintype "passive"))
    )
    (net (code "44") (name "/GPIO34") (class "Default")
      (node (ref "J2") (pin "16") (pinfunction "16_16") (pintype "passive"))
      (node (ref "U1") (pin "29") (pinfunction "GPIO34/SPIIO5/FSPICS0/SUBSPICS0_29") (pintype "passive"))
    )
    (net (code "45") (name "/GPIO35") (class "Default")
      (node (ref "J2") (pin "15") (pinfunction "15_15") (pintype "passive"))
      (node (ref "U1") (pin "31") (pinfunction "GPIO35/SPIIO6/FSPID/SUBSPID_31") (pintype "passive"))
    )
    (net (code "46") (name "/GPIO36") (class "Default")
      (node (ref "J2") (pin "14") (pinfunction "14_14") (pintype "passive"))
      (node (ref "U1") (pin "32") (pinfunction "GPIO36/SPIIO7/FSPICLK/SUBSPICLK_32") (pintype "passive"))
    )
    (net (code "47") (name "/GPIO37") (class "Default")
      (node (ref "J2") (pin "13") (pinfunction "13_13") (pintype "passive"))
      (node (ref "U1") (pin "33") (pinfunction "GPIO37/SPIDQS/FSPIQ/SUBSPIQ_33") (pintype "passive"))
    )
    (net (code "48") (name "/GPIO38") (class "Default")
      (node (ref "J2") (pin "12") (pinfunction "12_12") (pintype "passive"))
      (node (ref "U1") (pin "34") (pinfunction "GPIO38/FSPIWP/SUBSPIWP_34") (pintype "passive"))
    )
    (net (code "49") (name "/GPIO39") (class "Default")
      (node (ref "J2") (pin "11") (pinfunction "11_11") (pintype "passive"))
      (node (ref "U1") (pin "35") (pinfunction "MTCK/GPIO39/CLK_OUT3/SUBSPICS1_35") (pintype "passive"))
    )
    (net (code "50") (name "/GPIO40") (class "Default")
      (node (ref "J2") (pin "10") (pinfunction "10_10") (pintype "passive"))
      (node (ref "U1") (pin "36") (pinfunction "MTDO/GPIO40/CLK_OUT2_36") (pintype "passive"))
    )
    (net (code "51") (name "/GPIO41") (class "Default")
      (node (ref "J2") (pin "9") (pinfunction "9_9") (pintype "passive"))
      (node (ref "U1") (pin "37") (pinfunction "MTDI/GPIO41/CLK_OUT1_37") (pintype "passive"))
    )
    (net (code "52") (name "/GPIO42") (class "Default")
      (node (ref "J2") (pin "8") (pinfunction "8_8") (pintype "passive"))
      (node (ref "U1") (pin "38") (pinfunction "MTMS/GPIO42_38") (pintype "passive"))
    )
    (net (code "53") (name "/GPIO45") (class "Default")
      (node (ref "J2") (pin "5") (pinfunction "5_5") (pintype "passive"))
      (node (ref "U1") (pin "41") (pinfunction "GPIO45_41") (pintype "passive"))
    )
    (net (code "54") (name "/GPIO46") (class "Default")
      (node (ref "J2") (pin "4") (pinfunction "4_4") (pintype "passive"))
      (node (ref "U1") (pin "44") (pinfunction "GPIO46_44") (pintype "passive"))
    )
    (net (code "55") (name "/GPIO47") (class "Default")
      (node (ref "J2") (pin "23") (pinfunction "23_23") (pintype "passive"))
      (node (ref "U1") (pin "27") (pinfunction "GPIO47/SPICLK_P_DIFF/SUBSPICLK_P_DIFF_27") (pintype "passive"))
    )
    (net (code "56") (name "/GPIO48") (class "Default")
      (node (ref "J2") (pin "22") (pinfunction "22_22") (pintype "passive"))
      (node (ref "U1") (pin "30") (pinfunction "GPIO48/SPICLK_N_DIFF/SUBSPICLK_N_DIFF_30") (pintype "passive"))
    )
    (net (code "57") (name "/RTS_FTDI") (class "Default")
      (node (ref "Q1") (pin "2") (pinfunction "E_2") (pintype "passive"))
      (node (ref "R18") (pin "2") (pinfunction "2_2") (pintype "passive"))
      (node (ref "U2") (pin "19") (pinfunction "~{RTS}_19") (pintype "passive"))
    )
    (net (code "58") (name "/RXD_FTDI") (class "Default")
      (node (ref "R19") (pin "2") (pinfunction "2_2") (pintype "passive"))
      (node (ref "U2") (pin "1") (pinfunction "RXD_1") (pintype "passive"))
    )
    (net (code "59") (name "/TXD_FTDI") (class "Default")
      (node (ref "R20") (pin "2") (pinfunction "2_2") (pintype "passive"))
      (node (ref "U2") (pin "17") (pinfunction "TXD_17") (pintype "passive"))
    )
    (net (code "60") (name "/U0RXD") (class "Default")
      (node (ref "J2") (pin "6") (pinfunction "6_6") (pintype "passive"))
      (node (ref "R20") (pin "1") (pinfunction "1_1") (pintype "passive"))
      (node (ref "U1") (pin "40") (pinfunction "U0RXD/GPIO44/CLK_OUT2_40") (pintype "passive"))
    )
    (net (code "61") (name "/U0TXD") (class "Default")
      (node (ref "J2") (pin "7") (pinfunction "7_7") (pintype "passive"))
      (node (ref "R19") (pin "1") (pinfunction "1_1") (pintype "passive"))
      (node (ref "U1") (pin "39") (pinfunction "U0TXD/GPIO43/CLK_OUT1_39") (pintype "passive"))
    )
    (net (code "62") (name "/VBUS_SENSE") (class "Default")
      (node (ref "R10") (pin "1") (pinfunction "1_1") (pintype "passive"))
      (node (ref "R13") (pin "2") (pinfunction "2_2") (pintype "passive"))
      (node (ref "U2") (pin "16") (pinfunction "CBUS3_16") (pintype "passive"))
    )
    (net (code "63") (name "GND") (class "Default")
      (node (ref "C1") (pin "1") (pinfunction "1_1") (pintype "passive"))
      (node (ref "C10") (pin "1") (pinfunction "1_1") (pintype "passive"))
      (node (ref "C11") (pin "1") (pinfunction "1_1") (pintype "passive"))
      (node (ref "C12") (pin "1") (pinfunction "1_1") (pintype "passive"))
      (node (ref "C13") (pin "1") (pinfunction "1_1") (pintype "passive"))
      (node (ref "C14") (pin "1") (pinfunction "1_1") (pintype "passive"))
      (node (ref "C15") (pin "1") (pinfunction "1_1") (pintype "passive"))
      (node (ref "C16") (pin "1") (pinfunction "1_1") (pintype "passive"))
      (node (ref "C17") (pin "1") (pinfunction "1_1") (pintype "passive"))
      (node (ref "C2") (pin "1") (pinfunction "1_1") (pintype "passive"))
      (node (ref "C3") (pin "1") (pinfunction "1_1") (pintype "passive"))
      (node (ref "C4") (pin "1") (pinfunction "1_1") (pintype "passive"))
      (node (ref "C5") (pin "1") (pinfunction "1_1") (pintype "passive"))
      (node (ref "C6") (pin "1") (pinfunction "1_1") (pintype "passive"))
      (node (ref "C7") (pin "1") (pinfunction "1_1") (pintype "passive"))
      (node (ref "C8") (pin "1") (pinfunction "1_1") (pintype "passive"))
      (node (ref "C9") (pin "1") (pinfunction "1_1") (pintype "passive"))
      (node (ref "D1") (pin "1") (pinfunction "1_1") (pintype "passive"))
      (node (ref "D3") (pin "1") (pinfunction "1_1") (pintype "passive"))
      (node (ref "D4") (pin "1") (pinfunction "1_1") (pintype "passive"))
      (node (ref "D5") (pin "1") (pinfunction "1_1") (pintype "passive"))
      (node (ref "D6") (pin "1") (pinfunction "1_1") (pintype "passive"))
      (node (ref "D7") (pin "1") (pinfunction "1_1") (pintype "passive"))
      (node (ref "D8") (pin "1") (pinfunction "1_1") (pintype "passive"))
      (node (ref "J1") (pin "1") (pinfunction "1_1") (pintype "passive"))
      (node (ref "J1") (pin "23") (pinfunction "23_23") (pintype "passive"))
      (node (ref "J2") (pin "2") (pinfunction "2_2") (pintype "passive"))
      (node (ref "J2") (pin "24") (pinfunction "24_24") (pintype "passive"))
      (node (ref "J3") (pin "A1B12") (pinfunction "GND_A1B12_A1B12") (pintype "passive"))
      (node (ref "J3") (pin "B1A12") (pinfunction "GND_B1A12_B1A12") (pintype "passive"))
      (node (ref "J3") (pin "S1") (pinfunction "SHIELD_1_S1") (pintype "passive"))
      (node (ref "J3") (pin "S2") (pinfunction "SHIELD_2_S2") (pintype "passive"))
      (node (ref "J3") (pin "S3") (pinfunction "SHIELD_3_S3") (pintype "passive"))
      (node (ref "J3") (pin "S4") (pinfunction "SHIELD_4_S4") (pintype "passive"))
      (node (ref "J4") (pin "A1B12") (pinfunction "GND_A1B12_A1B12") (pintype "passive"))
      (node (ref "J4") (pin "B1A12") (pinfunction "GND_B1A12_B1A12") (pintype "passive"))
      (node (ref "J4") (pin "S1") (pinfunction "SHIELD_1_S1") (pintype "passive"))
      (node (ref "J4") (pin "S2") (pinfunction "SHIELD_2_S2") (pintype "passive"))
      (node (ref "J4") (pin "S3") (pinfunction "SHIELD_3_S3") (pintype "passive"))
      (node (ref "J4") (pin "S4") (pinfunction "SHIELD_4_S4") (pintype "passive"))
      (node (ref "R11") (pin "1") (pinfunction "1_1") (pintype "passive"))
      (node (ref "R12") (pin "1") (pinfunction "1_1") (pintype "passive"))
      (node (ref "R13") (pin "1") (pinfunction "1_1") (pintype "passive"))
      (node (ref "R14") (pin "1") (pinfunction "1_1") (pintype "passive"))
      (node (ref "R15") (pin "1") (pinfunction "1_1") (pintype "passive"))
      (node (ref "R9") (pin "1") (pinfunction "1_1") (pintype "passive"))
      (node (ref "SW1") (pin "3") (pinfunction "3_3") (pintype "passive"))
      (node (ref "SW1") (pin "4") (pinfunction "4_4") (pintype "passive"))
      (node (ref "SW2") (pin "3") (pinfunction "3_3") (pintype "passive"))
      (node (ref "SW2") (pin "4") (pinfunction "4_4") (pintype "passive"))
      (node (ref "U1") (pin "1") (pinfunction "GND_01_1") (pintype "passive"))
      (node (ref "U1") (pin "2") (pinfunction "GND_02_2") (pintype "passive"))
      (node (ref "U1") (pin "42") (pinfunction "GND_42") (pintype "passive"))
      (node (ref "U1") (pin "43") (pinfunction "GND_43") (pintype "passive"))
      (node (ref "U1") (pin "46") (pinfunction "GND_46_46") (pintype "passive"))
      (node (ref "U1") (pin "47") (pinfunction "GND_47_47") (pintype "passive"))
      (node (ref "U1") (pin "48") (pinfunction "GND_48_48") (pintype "passive"))
      (node (ref "U1") (pin "49") (pinfunction "GND_49_49") (pintype "passive"))
      (node (ref "U1") (pin "50") (pinfunction "GND_50_50") (pintype "passive"))
      (node (ref "U1") (pin "51") (pinfunction "GND_51_51") (pintype "passive"))
      (node (ref "U1") (pin "52") (pinfunction "GND_52_52") (pintype "passive"))
      (node (ref "U1") (pin "53") (pinfunction "GND_53_53") (pintype "passive"))
      (node (ref "U1") (pin "54") (pinfunction "GND_54_54") (pintype "passive"))
      (node (ref "U1") (pin "55") (pinfunction "GND_55_55") (pintype "passive"))
      (node (ref "U1") (pin "56") (pinfunction "GND_56_56") (pintype "passive"))
      (node (ref "U1") (pin "57") (pinfunction "GND_57_57") (pintype "passive"))
      (node (ref "U1") (pin "58") (pinfunction "GND_58_58") (pintype "passive"))
      (node (ref "U1") (pin "59") (pinfunction "GND_59_59") (pintype "passive"))
      (node (ref "U1") (pin "60") (pinfunction "GND_60_60") (pintype "passive"))
      (node (ref "U1") (pin "61") (pinfunction "GND_61_61") (pintype "passive"))
      (node (ref "U1") (pin "62") (pinfunction "GND_62_62") (pintype "passive"))
      (node (ref "U1") (pin "63") (pinfunction "GND_63_63") (pintype "passive"))
      (node (ref "U1") (pin "64") (pinfunction "GND_64_64") (pintype "passive"))
      (node (ref "U1") (pin "65") (pinfunction "GND_65_65") (pintype "passive"))
      (node (ref "U1") (pin "66") (pinfunction "GND_66_66") (pintype "passive"))
      (node (ref "U1") (pin "67") (pinfunction "GND_67_67") (pintype "passive"))
      (node (ref "U1") (pin "68") (pinfunction "GND_68_68") (pintype "passive"))
      (node (ref "U1") (pin "69") (pinfunction "GND_69_69") (pintype "passive"))
      (node (ref "U1") (pin "70") (pinfunction "GND_70_70") (pintype "passive"))
      (node (ref "U1") (pin "71") (pinfunction "GND_71_71") (pintype "passive"))
      (node (ref "U1") (pin "72") (pinfunction "GND_72_72") (pintype "passive"))
      (node (ref "U1") (pin "73") (pinfunction "GND_73_73") (pintype "passive"))
      (node (ref "U2") (pin "13") (pinfunction "GND_13") (pintype "passive"))
      (node (ref "U2") (pin "21") (pinfunction "GND_21") (pintype "passive"))
      (node (ref "U2") (pin "3") (pinfunction "GND_3") (pintype "passive"))
      (node (ref "U3") (pin "2") (pinfunction "GND_2") (pintype "power_in"))
      (node (ref "U3") (pin "4") (pinfunction "GND_4") (pintype "power_in"))
    )
    (net (code "64") (name "Net-(D1-Pad2)") (class "Default")
      (node (ref "D1") (pin "2") (pinfunction "2_2") (pintype "passive"))
      (node (ref "R3") (pin "1") (pinfunction "1_1") (pintype "passive"))
    )
    (net (code "65") (name "Net-(D2-Pad2)") (class "Default")
      (node (ref "D2") (pin "2") (pinfunction "2_2") (pintype "passive"))
      (node (ref "R4") (pin "1") (pinfunction "1_1") (pintype "passive"))
    )
    (net (code "66") (name "Net-(J3-CC1)") (class "Default")
      (node (ref "J3") (pin "A5") (pinfunction "CC1_A5") (pintype "passive"))
      (node (ref "R12") (pin "2") (pinfunction "2_2") (pintype "passive"))
    )
    (net (code "67") (name "Net-(J3-CC2)") (class "Default")
      (node (ref "J3") (pin "B5") (pinfunction "CC2_B5") (pintype "passive"))
      (node (ref "R11") (pin "2") (pinfunction "2_2") (pintype "passive"))
    )
    (net (code "68") (name "Net-(J4-CC1)") (class "Default")
      (node (ref "J4") (pin "A5") (pinfunction "CC1_A5") (pintype "passive"))
      (node (ref "R15") (pin "2") (pinfunction "2_2") (pintype "passive"))
    )
    (net (code "69") (name "Net-(J4-CC2)") (class "Default")
      (node (ref "J4") (pin "B5") (pinfunction "CC2_B5") (pintype "passive"))
      (node (ref "R14") (pin "2") (pinfunction "2_2") (pintype "passive"))
    )
    (net (code "70") (name "Net-(Q1-B)") (class "Default")
      (node (ref "Q1") (pin "1") (pinfunction "B_1") (pintype "passive"))
      (node (ref "R16") (pin "1") (pinfunction "1_1") (pintype "passive"))
    )
    (net (code "71") (name "Net-(Q2-B)") (class "Default")
      (node (ref "Q2") (pin "1") (pinfunction "B_1") (pintype "passive"))
      (node (ref "R18") (pin "1") (pinfunction "1_1") (pintype "passive"))
    )
    (net (code "72") (name "Net-(U2-CBUS0)") (class "Default")
      (node (ref "R9") (pin "2") (pinfunction "2_2") (pintype "passive"))
      (node (ref "U2") (pin "15") (pinfunction "CBUS0_15") (pintype "passive"))
    )
    (net (code "73") (name "Net-(U2-~{RESET})") (class "Default")
      (node (ref "C7") (pin "2") (pinfunction "2_2") (pintype "passive"))
      (node (ref "R8") (pin "2") (pinfunction "2_2") (pintype "passive"))
      (node (ref "U2") (pin "11") (pinfunction "~{RESET}_11") (pintype "passive"))
    )
    (net (code "74") (name "unconnected-(C14-Pad2)") (class "Default")
      (node (ref "C14") (pin "2") (pinfunction "2_2") (pintype "passive"))
    )
    (net (code "75") (name "unconnected-(J1-Pad24)") (class "Default")
      (node (ref "J1") (pin "24") (pinfunction "24_24") (pintype "passive+no_connect"))
    )
    (net (code "76") (name "unconnected-(J3-SBU1-PadA8)") (class "Default")
      (node (ref "J3") (pin "A8") (pinfunction "SBU1_A8") (pintype "passive+no_connect"))
    )
    (net (code "77") (name "unconnected-(J3-SBU2-PadB8)") (class "Default")
      (node (ref "J3") (pin "B8") (pinfunction "SBU2_B8") (pintype "passive+no_connect"))
    )
    (net (code "78") (name "unconnected-(J4-SBU1-PadA8)") (class "Default")
      (node (ref "J4") (pin "A8") (pinfunction "SBU1_A8") (pintype "passive+no_connect"))
    )
    (net (code "79") (name "unconnected-(J4-SBU2-PadB8)") (class "Default")
      (node (ref "J4") (pin "B8") (pinfunction "SBU2_B8") (pintype "passive+no_connect"))
    )
    (net (code "80") (name "unconnected-(U2-CBUS1-Pad14)") (class "Default")
      (node (ref "U2") (pin "14") (pinfunction "CBUS1_14") (pintype "passive"))
    )
    (net (code "81") (name "unconnected-(U2-CBUS2-Pad7)") (class "Default")
      (node (ref "U2") (pin "7") (pinfunction "CBUS2_7") (pintype "passive"))
    )
    (net (code "82") (name "unconnected-(U2-~{CTS}-Pad6)") (class "Default")
      (node (ref "U2") (pin "6") (pinfunction "~{CTS}_6") (pintype "passive+no_connect"))
    )
    (net (code "83") (name "unconnected-(U2-~{DCD}-Pad5)") (class "Default")
      (node (ref "U2") (pin "5") (pinfunction "~{DCD}_5") (pintype "passive+no_connect"))
    )
    (net (code "84") (name "unconnected-(U2-~{DSR}-Pad4)") (class "Default")
      (node (ref "U2") (pin "4") (pinfunction "~{DSR}_4") (pintype "passive+no_connect"))
    )
    (net (code "85") (name "unconnected-(U2-~{RI}-Pad2)") (class "Default")
      (node (ref "U2") (pin "2") (pinfunction "~{RI}_2") (pintype "passive+no_connect"))
    )
  )
)
